# Mabee_Button_V1_1.net
KiCad netlist of a schematic drawn in EAGLE
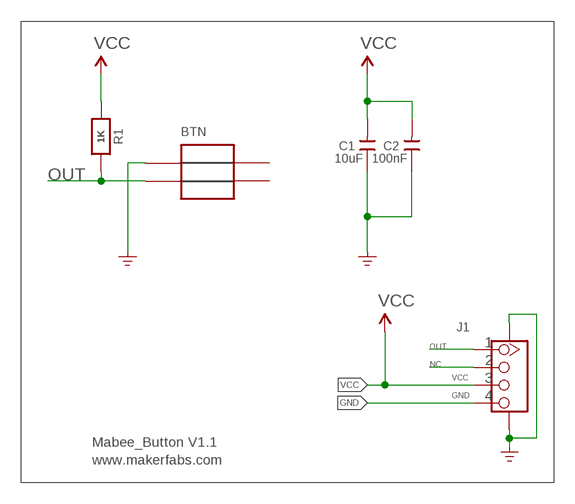
[diagram p0: schematic, sheet 1]

(export (version "E")
  (design (tool "Eeschema 10.0.6"))
  (components
    (comp (ref "BTN")
      (value "BUTTON_1212")
      (footprint "eagle-import:12_12_BUTTON_DIP")
      (libsource (lib "eagle-import") (part "BUTTON_1212"))
    )
    (comp (ref "C1")
      (value "10uF")
      (footprint "eagle-import:0603")
      (libsource (lib "eagle-import") (part "C-0603"))
    )
    (comp (ref "C2")
      (value "100nF")
      (footprint "eagle-import:0603")
      (libsource (lib "eagle-import") (part "C-0603"))
    )
    (comp (ref "J1")
      (value "GROVE-CONNECTOR-SMD'90D'")
      (footprint "eagle-import:HW4-SMD-2.0-90D")
      (libsource (lib "eagle-import") (part "GROVE-CONNECTOR-SMD'90D'"))
    )
    (comp (ref "R1")
      (value "1K")
      (footprint "eagle-import:0603-NO")
      (libsource (lib "eagle-import") (part "RESISTOR_0603_NOOUT"))
    )
  )
  (nets
    (net (code "1") (name "/NC") (class "Default")
      (node (ref "J1") (pin "2") (pinfunction "2_2") (pintype "bidirectional"))
    )
    (net (code "2") (name "/OUT") (class "Default")
      (node (ref "BTN") (pin "3") (pinfunction "3_3") (pintype "bidirectional"))
      (node (ref "J1") (pin "1") (pinfunction "1_1") (pintype "bidirectional"))
      (node (ref "R1") (pin "2") (pinfunction "2_2") (pintype "passive"))
    )
    (net (code "3") (name "GND") (class "Default")
      (node (ref "BTN") (pin "1") (pinfunction "1_1") (pintype "bidirectional"))
      (node (ref "C1") (pin "1") (pinfunction "1_1") (pintype "passive"))
      (node (ref "C2") (pin "1") (pinfunction "1_1") (pintype "passive"))
      (node (ref "J1") (pin "4") (pinfunction "4_4") (pintype "bidirectional"))
      (node (ref "J1") (pin "SS1") (pinfunction "SS1_SS1") (pintype "bidirectional"))
      (node (ref "J1") (pin "SS2") (pinfunction "SS2_SS2") (pintype "bidirectional"))
    )
    (net (code "4") (name "VCC") (class "Default")
      (node (ref "C1") (pin "2") (pinfunction "2_2") (pintype "passive"))
      (node (ref "C2") (pin "2") (pinfunction "2_2") (pintype "passive"))
      (node (ref "J1") (pin "3") (pinfunction "3_3") (pintype "bidirectional"))
      (node (ref "R1") (pin "1") (pinfunction "1_1") (pintype "passive"))
    )
    (net (code "5") (name "unconnected-(BTN-Pad2)") (class "Default")
      (node (ref "BTN") (pin "2") (pinfunction "2_2") (pintype "bidirectional"))
    )
    (net (code "6") (name "unconnected-(BTN-Pad4)") (class "Default")
      (node (ref "BTN") (pin "4") (pinfunction "4_4") (pintype "bidirectional"))
    )
  )
)
